# JTAG_Trace.net
KiCad netlist of a schematic drawn in Altium Designer
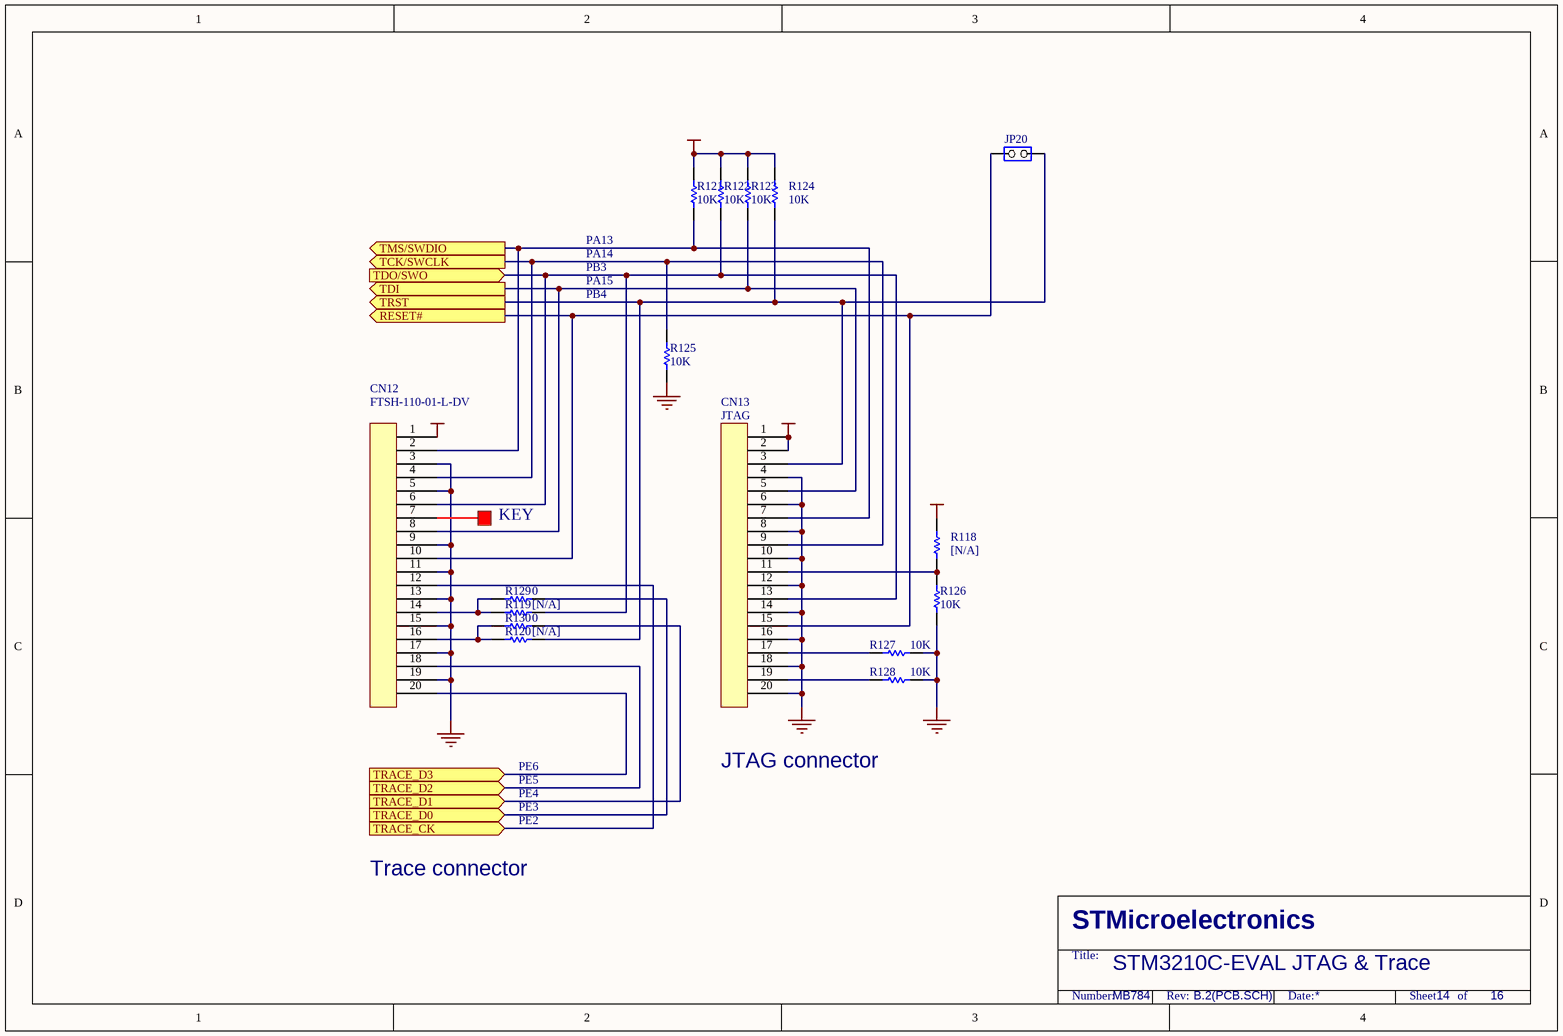
[diagram p0: JTAG&Trace.SchDoc]

(export (version "E")
  (design (tool "Eeschema 10.0.6"))
  (components
    (comp (ref "CN12")
      (value "FTSH-110-01-L-DV")
      (footprint "FTSH-110-01-L-DV")
      (libsource (lib "*") (part "20PIN1"))
    )
    (comp (ref "CN13") (value "JTAG") (footprint "IDC20S") (libsource (lib "*") (part "20PIN1")))
    (comp (ref "JP20") (value "~") (footprint "SIP2") (libsource (lib "*") (part "JP2")))
    (comp (ref "R118")
      (value "[N/A]")
      (footprint "0603R")
      (description "Resistor")
      (fields (field (name "PUBLISHER") "Altium Limited"))
      (libsource (lib "Miscellaneous Devices") (part "Res1"))
    )
    (comp (ref "R119")
      (value "[N/A]")
      (footprint "0603R")
      (description "Resistor")
      (fields (field (name "PUBLISHER") "Altium Limited"))
      (libsource (lib "Miscellaneous Devices") (part "Res1"))
    )
    (comp (ref "R120")
      (value "[N/A]")
      (footprint "0603R")
      (description "Resistor")
      (fields (field (name "PUBLISHER") "Altium Limited"))
      (libsource (lib "Miscellaneous Devices") (part "Res1"))
    )
    (comp (ref "R121")
      (value "10K")
      (footprint "0603R")
      (description "Resistor")
      (fields (field (name "PUBLISHER") "Altium Limited"))
      (libsource (lib "Miscellaneous Devices") (part "Res1"))
    )
    (comp (ref "R122")
      (value "10K")
      (footprint "0603R")
      (description "Resistor")
      (fields (field (name "PUBLISHER") "Altium Limited"))
      (libsource (lib "Miscellaneous Devices") (part "Res1"))
    )
    (comp (ref "R123")
      (value "10K")
      (footprint "0603R")
      (description "Resistor")
      (fields (field (name "PUBLISHER") "Altium Limited"))
      (libsource (lib "Miscellaneous Devices") (part "Res1"))
    )
    (comp (ref "R124")
      (value "10K")
      (footprint "0603R")
      (description "Resistor")
      (fields (field (name "PUBLISHER") "Altium Limited"))
      (libsource (lib "Miscellaneous Devices") (part "Res1"))
    )
    (comp (ref "R125")
      (value "10K")
      (footprint "0603R")
      (description "Resistor")
      (fields (field (name "PUBLISHER") "Altium Limited"))
      (libsource (lib "Miscellaneous Devices") (part "Res1"))
    )
    (comp (ref "R126")
      (value "10K")
      (footprint "0603R")
      (description "Resistor")
      (fields (field (name "PUBLISHER") "Altium Limited"))
      (libsource (lib "Miscellaneous Devices") (part "Res1"))
    )
    (comp (ref "R127")
      (value "10K")
      (footprint "0603R")
      (description "Resistor")
      (fields (field (name "PUBLISHER") "Altium Limited"))
      (libsource (lib "Miscellaneous Devices") (part "Res1"))
    )
    (comp (ref "R128")
      (value "10K")
      (footprint "0603R")
      (description "Resistor")
      (fields (field (name "PUBLISHER") "Altium Limited"))
      (libsource (lib "Miscellaneous Devices") (part "Res1"))
    )
    (comp (ref "R129")
      (value "0")
      (footprint "0603R")
      (description "Resistor")
      (fields (field (name "PUBLISHER") "Altium Limited"))
      (libsource (lib "Miscellaneous Devices") (part "Res1"))
    )
    (comp (ref "R130")
      (value "0")
      (footprint "0603R")
      (description "Resistor")
      (fields (field (name "PUBLISHER") "Altium Limited"))
      (libsource (lib "Miscellaneous Devices") (part "Res1"))
    )
  )
  (nets
    (net (code "1") (name "+3V3") (class "Default")
      (node (ref "CN12") (pin "1") (pintype "passive"))
      (node (ref "CN13") (pin "1") (pintype "passive"))
      (node (ref "CN13") (pin "2") (pintype "passive"))
      (node (ref "R118") (pin "2") (pinfunction "2_2") (pintype "passive"))
      (node (ref "R121") (pin "2") (pinfunction "2_2") (pintype "passive"))
      (node (ref "R122") (pin "2") (pinfunction "2_2") (pintype "passive"))
      (node (ref "R123") (pin "2") (pinfunction "2_2") (pintype "passive"))
      (node (ref "R124") (pin "2") (pinfunction "2_2") (pintype "passive"))
    )
    (net (code "2") (name "/RESET#") (class "Default")
      (node (ref "CN12") (pin "10") (pintype "passive"))
      (node (ref "CN13") (pin "15") (pintype "passive"))
      (node (ref "JP20") (pin "2") (pinfunction "NO_2") (pintype "passive"))
    )
    (net (code "3") (name "/TCK{slash}SWCLK") (class "Default")
      (node (ref "CN12") (pin "4") (pintype "passive"))
      (node (ref "CN13") (pin "9") (pintype "passive"))
      (node (ref "R125") (pin "2") (pinfunction "2_2") (pintype "passive"))
    )
    (net (code "4") (name "/TDI") (class "Default")
      (node (ref "CN12") (pin "8") (pintype "passive"))
      (node (ref "CN13") (pin "5") (pintype "passive"))
      (node (ref "R123") (pin "1") (pinfunction "1_1") (pintype "passive"))
    )
    (net (code "5") (name "/TDO{slash}SWO") (class "Default")
      (node (ref "CN12") (pin "6") (pintype "passive"))
      (node (ref "CN13") (pin "13") (pintype "passive"))
      (node (ref "R119") (pin "2") (pinfunction "2_2") (pintype "passive"))
      (node (ref "R122") (pin "1") (pinfunction "1_1") (pintype "passive"))
    )
    (net (code "6") (name "/TMS{slash}SWDIO") (class "Default")
      (node (ref "CN12") (pin "2") (pintype "passive"))
      (node (ref "CN13") (pin "7") (pintype "passive"))
      (node (ref "R121") (pin "1") (pinfunction "1_1") (pintype "passive"))
    )
    (net (code "7") (name "/TRACE_CK") (class "Default") (node (ref "CN12") (pin "12") (pintype "passive")))
    (net (code "8") (name "/TRACE_D0") (class "Default")
      (node (ref "R129") (pin "2") (pinfunction "2_2") (pintype "passive"))
    )
    (net (code "9") (name "/TRACE_D1") (class "Default")
      (node (ref "R130") (pin "2") (pinfunction "2_2") (pintype "passive"))
    )
    (net (code "10") (name "/TRACE_D2") (class "Default") (node (ref "CN12") (pin "18") (pintype "passive")))
    (net (code "11") (name "/TRACE_D3") (class "Default") (node (ref "CN12") (pin "20") (pintype "passive")))
    (net (code "12") (name "/TRST") (class "Default")
      (node (ref "CN13") (pin "3") (pintype "passive"))
      (node (ref "JP20") (pin "1") (pinfunction "COMMON_1") (pintype "passive"))
      (node (ref "R120") (pin "2") (pinfunction "2_2") (pintype "passive"))
      (node (ref "R124") (pin "1") (pinfunction "1_1") (pintype "passive"))
    )
    (net (code "13") (name "GND") (class "Default")
      (node (ref "CN12") (pin "11") (pintype "passive"))
      (node (ref "CN12") (pin "13") (pintype "passive"))
      (node (ref "CN12") (pin "15") (pintype "passive"))
      (node (ref "CN12") (pin "17") (pintype "passive"))
      (node (ref "CN12") (pin "19") (pintype "passive"))
      (node (ref "CN12") (pin "3") (pintype "passive"))
      (node (ref "CN12") (pin "5") (pintype "passive"))
      (node (ref "CN12") (pin "9") (pintype "passive"))
      (node (ref "CN13") (pin "10") (pintype "passive"))
      (node (ref "CN13") (pin "12") (pintype "passive"))
      (node (ref "CN13") (pin "14") (pintype "passive"))
      (node (ref "CN13") (pin "16") (pintype "passive"))
      (node (ref "CN13") (pin "18") (pintype "passive"))
      (node (ref "CN13") (pin "20") (pintype "passive"))
      (node (ref "CN13") (pin "4") (pintype "passive"))
      (node (ref "CN13") (pin "6") (pintype "passive"))
      (node (ref "CN13") (pin "8") (pintype "passive"))
      (node (ref "R125") (pin "1") (pinfunction "1_1") (pintype "passive"))
      (node (ref "R126") (pin "1") (pinfunction "1_1") (pintype "passive"))
      (node (ref "R127") (pin "2") (pinfunction "2_2") (pintype "passive"))
      (node (ref "R128") (pin "2") (pinfunction "2_2") (pintype "passive"))
    )
    (net (code "14") (name "Net-(CN12-Pad14)") (class "Default")
      (node (ref "CN12") (pin "14") (pintype "passive"))
      (node (ref "R119") (pin "1") (pinfunction "1_1") (pintype "passive"))
      (node (ref "R129") (pin "1") (pinfunction "1_1") (pintype "passive"))
    )
    (net (code "15") (name "Net-(CN12-Pad16)") (class "Default")
      (node (ref "CN12") (pin "16") (pintype "passive"))
      (node (ref "R120") (pin "1") (pinfunction "1_1") (pintype "passive"))
      (node (ref "R130") (pin "1") (pinfunction "1_1") (pintype "passive"))
    )
    (net (code "16") (name "Net-(CN13-Pad11)") (class "Default")
      (node (ref "CN13") (pin "11") (pintype "passive"))
      (node (ref "R118") (pin "1") (pinfunction "1_1") (pintype "passive"))
      (node (ref "R126") (pin "2") (pinfunction "2_2") (pintype "passive"))
    )
    (net (code "17") (name "Net-(CN13-Pad17)") (class "Default")
      (node (ref "CN13") (pin "17") (pintype "passive"))
      (node (ref "R127") (pin "1") (pinfunction "1_1") (pintype "passive"))
    )
    (net (code "18") (name "Net-(CN13-Pad19)") (class "Default")
      (node (ref "CN13") (pin "19") (pintype "passive"))
      (node (ref "R128") (pin "1") (pinfunction "1_1") (pintype "passive"))
    )
    (net (code "19") (name "unconnected-(CN12-Pad7)") (class "Default")
      (node (ref "CN12") (pin "7") (pintype "passive"))
    )
  )
)
